# Input_Section.net
KiCad netlist of a schematic drawn in Altium Designer
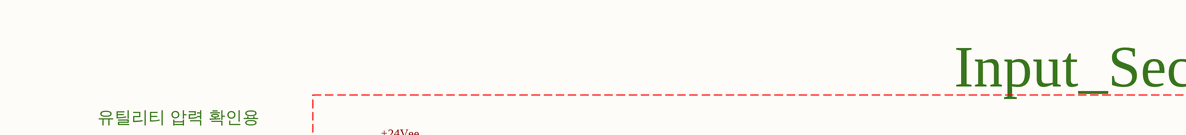
[diagram p0: Input_Section.SchDoc, top left]
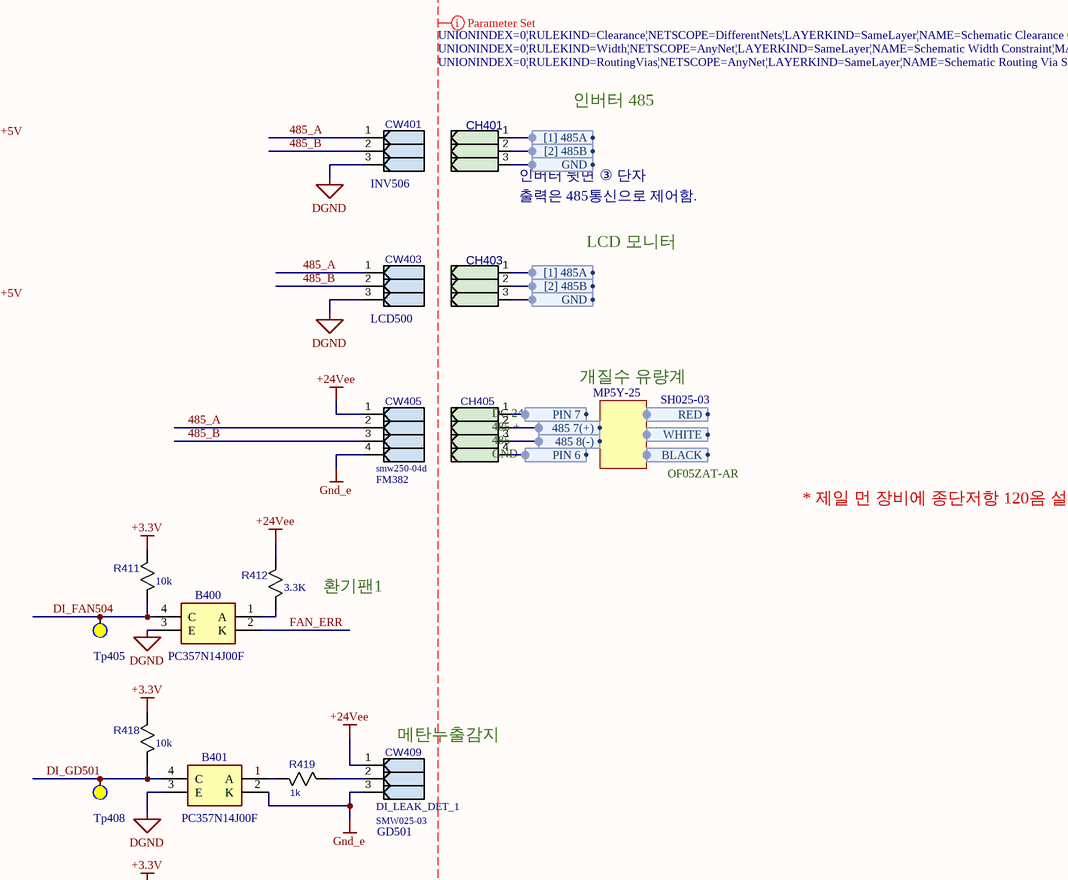
[diagram p1: Input_Section.SchDoc, top right]
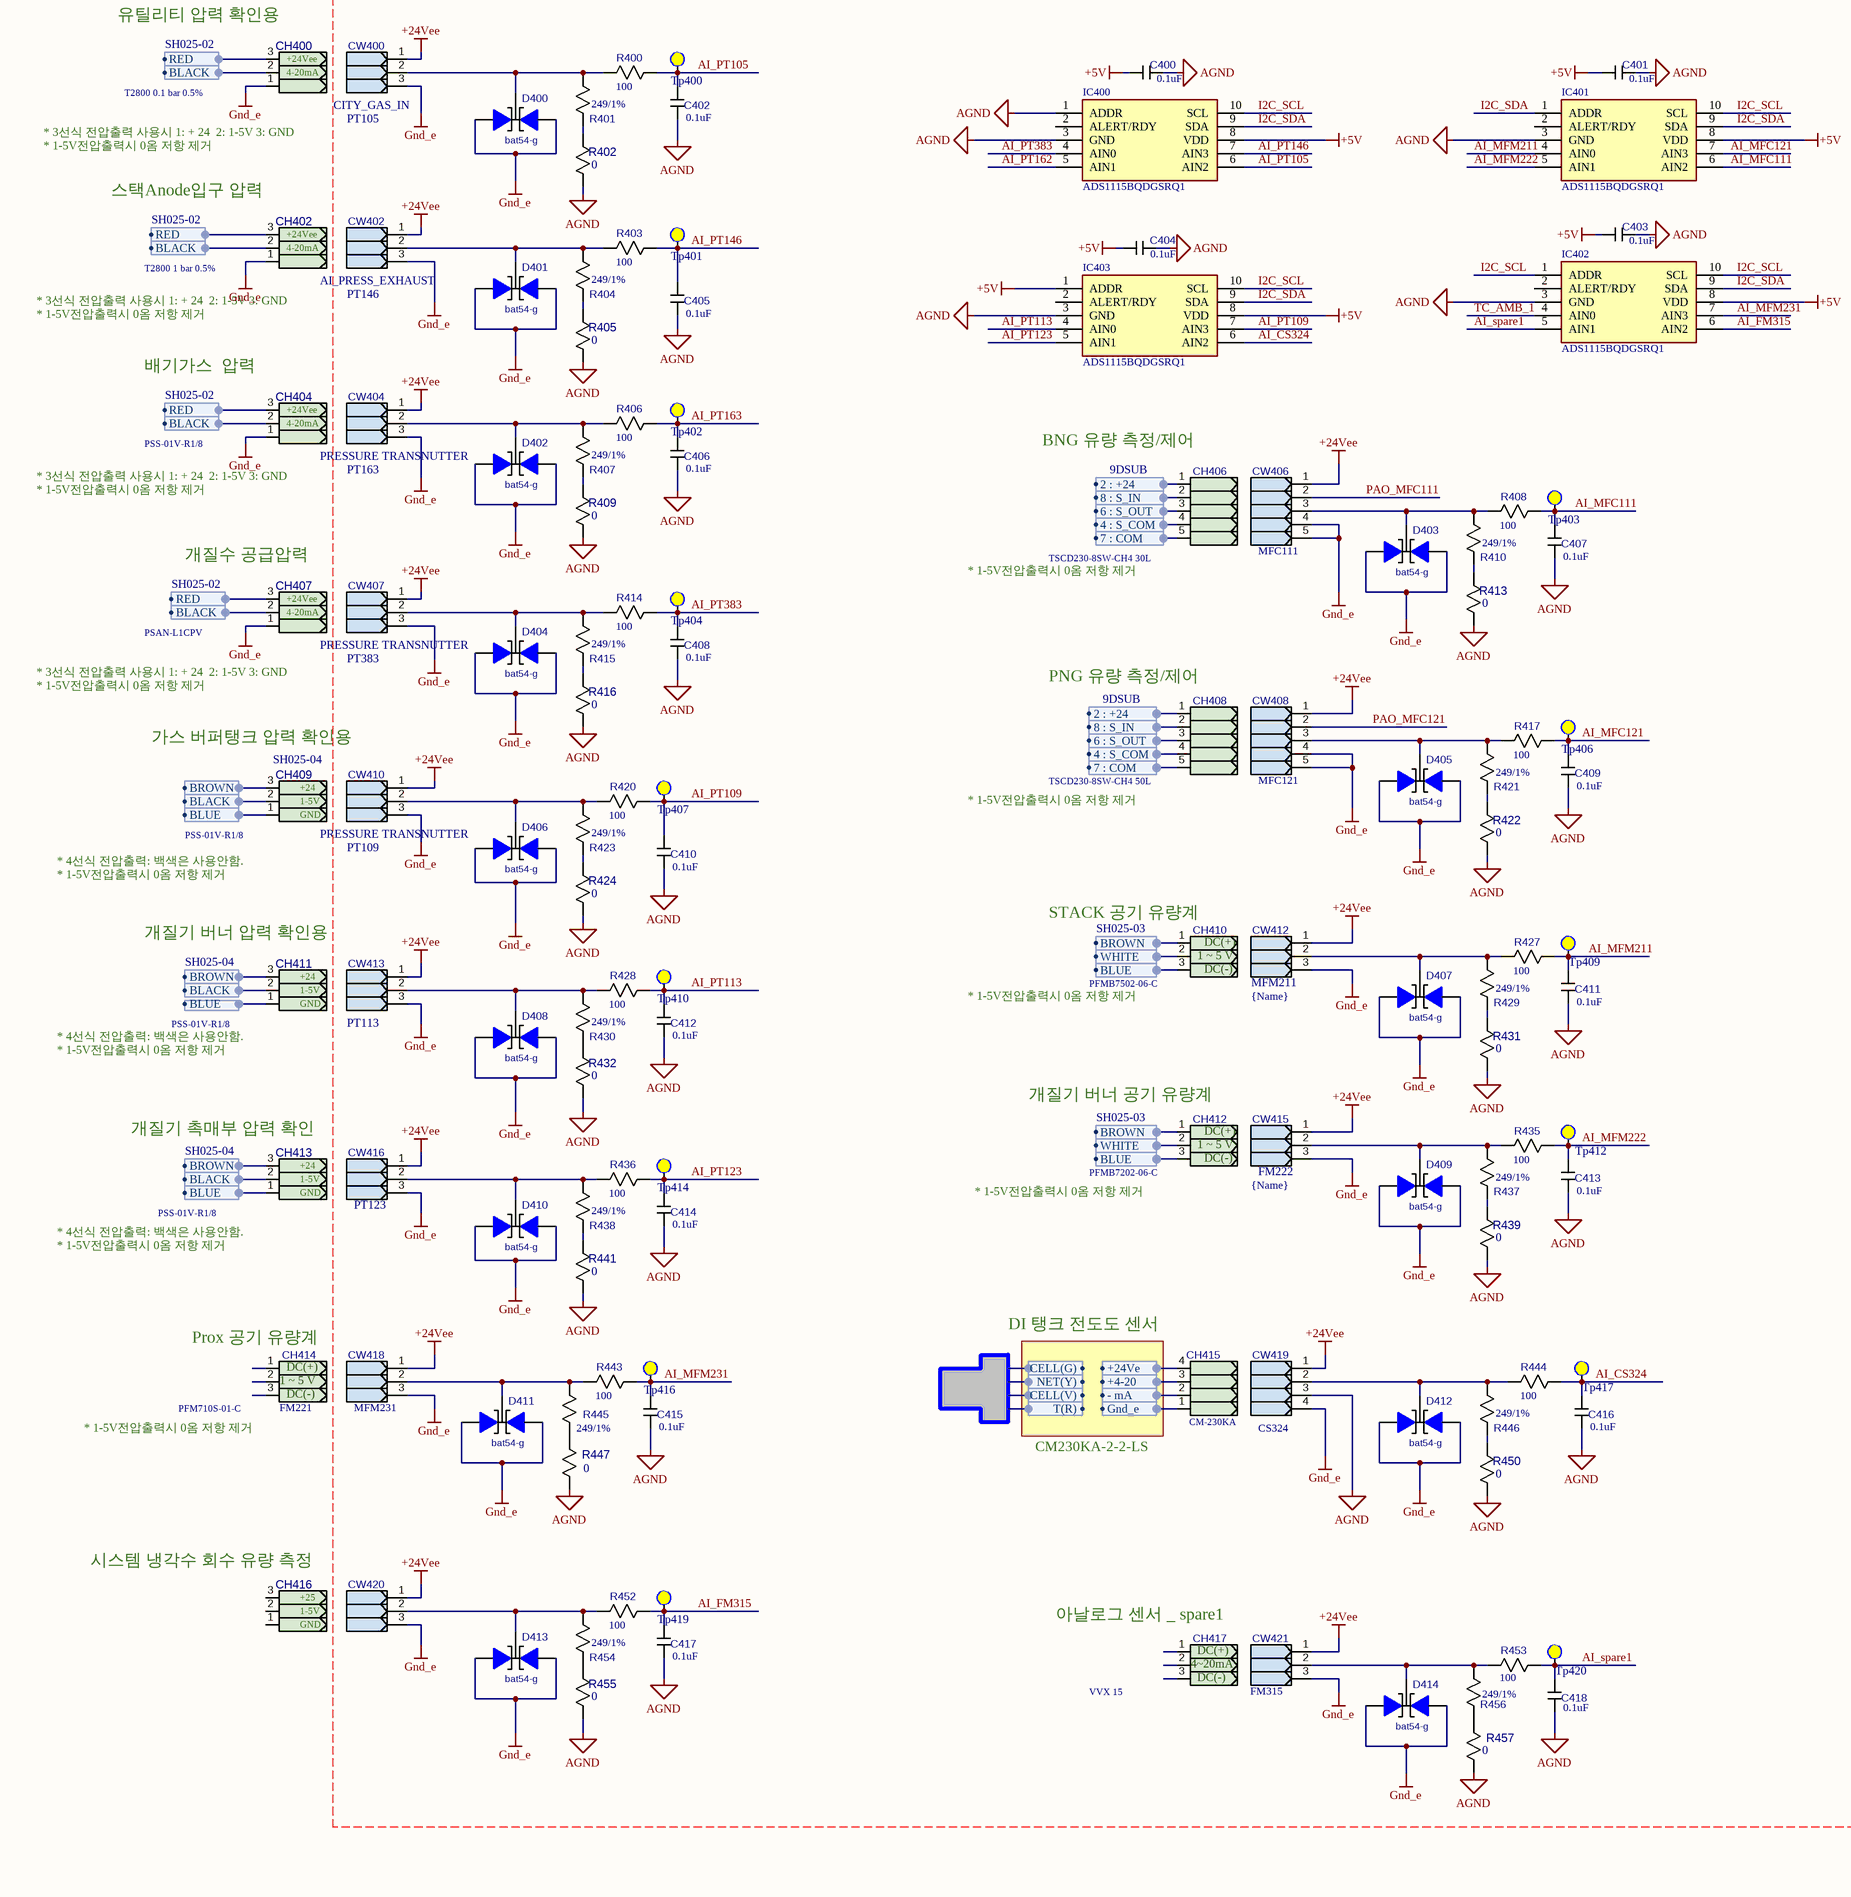
[diagram p2: Input_Section.SchDoc, bottom left]
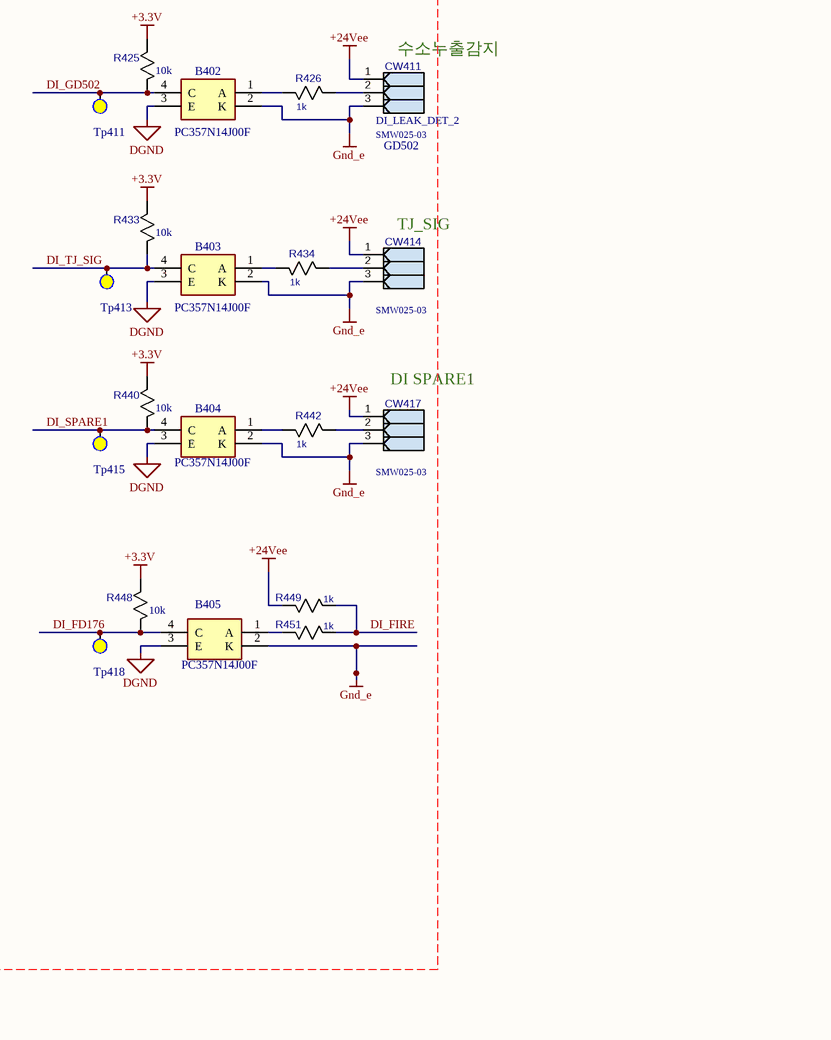
[diagram p3: Input_Section.SchDoc, bottom right]

(export (version "E")
  (design (tool "Eeschema 10.0.6"))
  (components
    (comp (ref "B400")
      (value "PC357N14J00F")
      (footprint "KipoAlt:SOP254P675X300-4N")
      (description "Integrated Circuit")
      (libsource (lib "KipoAlt") (part "PC357N14J00F"))
    )
    (comp (ref "B401")
      (value "PC357N14J00F")
      (footprint "KipoAlt:SOP254P675X300-4N")
      (description "Integrated Circuit")
      (libsource (lib "KipoAlt") (part "PC357N14J00F"))
    )
    (comp (ref "B402")
      (value "PC357N14J00F")
      (footprint "KipoAlt:SOP254P675X300-4N")
      (description "Integrated Circuit")
      (libsource (lib "KipoAlt") (part "PC357N14J00F"))
    )
    (comp (ref "B403")
      (value "PC357N14J00F")
      (footprint "KipoAlt:SOP254P675X300-4N")
      (description "Integrated Circuit")
      (libsource (lib "KipoAlt") (part "PC357N14J00F"))
    )
    (comp (ref "B404")
      (value "PC357N14J00F")
      (footprint "KipoAlt:SOP254P675X300-4N")
      (description "Integrated Circuit")
      (libsource (lib "KipoAlt") (part "PC357N14J00F"))
    )
    (comp (ref "B405")
      (value "PC357N14J00F")
      (footprint "KipoAlt:SOP254P675X300-4N")
      (description "Integrated Circuit")
      (libsource (lib "KipoAlt") (part "PC357N14J00F"))
    )
    (comp (ref "C400")
      (value "CS1608")
      (footprint "CC1608N")
      (fields (field (name "PART NO.") "{Part No}") (field (name "규격") "0.1uF"))
      (libsource (lib "KipoAlt") (part "CS1608"))
    )
    (comp (ref "C401")
      (value "CS1608")
      (footprint "CC1608N")
      (fields (field (name "PART NO.") "{Part No}") (field (name "규격") "0.1uF"))
      (libsource (lib "KipoAlt") (part "CS1608"))
    )
    (comp (ref "C402")
      (value "CS1608")
      (footprint "CC1608N")
      (fields (field (name "PART NO.") "{Part No}") (field (name "규격") "0.1uF"))
      (libsource (lib "KipoAlt") (part "CS1608"))
    )
    (comp (ref "C403")
      (value "CS1608")
      (footprint "CC1608N")
      (fields (field (name "PART NO.") "{Part No}") (field (name "규격") "0.1uF"))
      (libsource (lib "KipoAlt") (part "CS1608"))
    )
    (comp (ref "C404")
      (value "CS1608")
      (footprint "CC1608N")
      (fields (field (name "PART NO.") "{Part No}") (field (name "규격") "0.1uF"))
      (libsource (lib "KipoAlt") (part "CS1608"))
    )
    (comp (ref "C405")
      (value "CS1608")
      (footprint "CC1608N")
      (fields (field (name "PART NO.") "{Part No}") (field (name "규격") "0.1uF"))
      (libsource (lib "KipoAlt") (part "CS1608"))
    )
    (comp (ref "C406")
      (value "CS1608")
      (footprint "CC1608N")
      (fields (field (name "PART NO.") "{Part No}") (field (name "규격") "0.1uF"))
      (libsource (lib "KipoAlt") (part "CS1608"))
    )
    (comp (ref "C407")
      (value "CS1608")
      (footprint "CC1608N")
      (fields (field (name "PART NO.") "{Part No}") (field (name "규격") "0.1uF"))
      (libsource (lib "KipoAlt") (part "CS1608"))
    )
    (comp (ref "C408")
      (value "CS1608")
      (footprint "CC1608N")
      (fields (field (name "PART NO.") "{Part No}") (field (name "규격") "0.1uF"))
      (libsource (lib "KipoAlt") (part "CS1608"))
    )
    (comp (ref "C409")
      (value "CS1608")
      (footprint "CC1608N")
      (fields (field (name "PART NO.") "{Part No}") (field (name "규격") "0.1uF"))
      (libsource (lib "KipoAlt") (part "CS1608"))
    )
    (comp (ref "C410")
      (value "CS1608")
      (footprint "CC1608N")
      (fields (field (name "PART NO.") "{Part No}") (field (name "규격") "0.1uF"))
      (libsource (lib "KipoAlt") (part "CS1608"))
    )
    (comp (ref "C411")
      (value "CS1608")
      (footprint "CC1608N")
      (fields (field (name "PART NO.") "{Part No}") (field (name "규격") "0.1uF"))
      (libsource (lib "KipoAlt") (part "CS1608"))
    )
    (comp (ref "C412")
      (value "CS1608")
      (footprint "CC1608N")
      (fields (field (name "PART NO.") "{Part No}") (field (name "규격") "0.1uF"))
      (libsource (lib "KipoAlt") (part "CS1608"))
    )
    (comp (ref "C413")
      (value "CS1608")
      (footprint "CC1608N")
      (fields (field (name "PART NO.") "{Part No}") (field (name "규격") "0.1uF"))
      (libsource (lib "KipoAlt") (part "CS1608"))
    )
    (comp (ref "C414")
      (value "CS1608")
      (footprint "CC1608N")
      (fields (field (name "PART NO.") "{Part No}") (field (name "규격") "0.1uF"))
      (libsource (lib "KipoAlt") (part "CS1608"))
    )
    (comp (ref "C415")
      (value "CS1608")
      (footprint "CC1608N")
      (fields (field (name "PART NO.") "{Part No}") (field (name "규격") "0.1uF"))
      (libsource (lib "KipoAlt") (part "CS1608"))
    )
    (comp (ref "C416")
      (value "CS1608")
      (footprint "CC1608N")
      (fields (field (name "PART NO.") "{Part No}") (field (name "규격") "0.1uF"))
      (libsource (lib "KipoAlt") (part "CS1608"))
    )
    (comp (ref "C417")
      (value "CS1608")
      (footprint "CC1608N")
      (fields (field (name "PART NO.") "{Part No}") (field (name "규격") "0.1uF"))
      (libsource (lib "KipoAlt") (part "CS1608"))
    )
    (comp (ref "C418")
      (value "CS1608")
      (footprint "CC1608N")
      (fields (field (name "PART NO.") "{Part No}") (field (name "규격") "0.1uF"))
      (libsource (lib "KipoAlt") (part "CS1608"))
    )
    (comp (ref "CH400")
      (value "Connect Housing")
      (description "시티가스 공급압력 확인")
      (fields (field (name "PART NO.") "T2800 0.1 bar 0.5%"))
      (libsource (lib "KipoAlt") (part "CH_03"))
    )
    (comp (ref "CH401") (value "Connect Housing") (libsource (lib "") (part "CH_03_1")))
    (comp (ref "CH402")
      (value "Connect Housing")
      (description "시티가스 공급압력 확인")
      (fields (field (name "PART NO.") "T2800 1 bar 0.5%"))
      (libsource (lib "KipoAlt") (part "CH_03"))
    )
    (comp (ref "CH403") (value "Connect Housing") (libsource (lib "") (part "CH_03_1")))
    (comp (ref "CH404")
      (value "Connect Housing")
      (description "배기가스 출구 압력 측정\r\n\r\nO T2800 1 bar 0.5%")
      (fields (field (name "PART NO.") "PSS-01V-R1/8"))
      (libsource (lib "KipoAlt") (part "CH_03"))
    )
    (comp (ref "CH405")
      (value "Connect Housing")
      (description "개질수 유량계\r\n\r\n사용부품 : OF05ZAT-AR")
      (libsource (lib "KipoAlt") (part "CH_04"))
    )
    (comp (ref "CH406")
      (value "Connect Housing")
      (description "AI_PNG MFC\r\n\r\nTSCD230-6SW-CH4 30L")
      (fields (field (name "PART NO.") "TSCD230-8SW-CH4 30L"))
      (libsource (lib "KipoAlt") (part "CH_05"))
    )
    (comp (ref "CH407")
      (value "Connect Housing")
      (description "개질수 압력\r\n\r\nO T2800 10 bar 0.5%\r\nO 4~20mA\r\n\r\nO T2800 1 bar 0.5%")
      (fields (field (name "PART NO.") "PSAN-L1CPV"))
      (libsource (lib "KipoAlt") (part "CH_03"))
    )
    (comp (ref "CH408")
      (value "Connect Housing")
      (description "AI_PNG MFC\r\n\r\nTSCD230-6SW-CH4 30L")
      (fields (field (name "PART NO.") "TSCD230-8SW-CH4 50L"))
      (libsource (lib "KipoAlt") (part "CH_05"))
    )
    (comp (ref "CH409")
      (value "Connect Housing")
      (description "가압 버퍼탱크 압력 측정\r\n\r\n사용부품 : PSS-01A-R1/8\r\n\r\nO T2800 1 bar 0.5%")
      (fields (field (name "PART NO.") "PSS-01V-R1/8"))
      (libsource (lib "KipoAlt") (part "CH_03"))
    )
    (comp (ref "CH410")
      (value "Connect Housing")
      (description "스택 공기 유량계\r\n\r\nO PFMB7501-04-D\r\nO 1 ~ 5 V 입력 / 4~20mA")
      (fields (field (name "PART NO.") "PFMB7502-06-C"))
      (libsource (lib "") (part "CH_03_2"))
    )
    (comp (ref "CH411")
      (value "Connect Housing")
      (description "개질기 버너 압력 확인용\r\n\r\n사용부품 : PSS-01V-R1/8   \r\n\r\nO T2800 1 bar 0.5%")
      (fields (field (name "PART NO.") "PSS-01V-R1/8"))
      (libsource (lib "KipoAlt") (part "CH_03"))
    )
    (comp (ref "CH412")
      (value "Connect Housing")
      (description "스택 공기 유량계\r\n\r\nO PFMB7501-04-D\r\nO 1 ~ 5 V 입력 / 4~20mA")
      (fields (field (name "PART NO.") "PFMB7202-06-C"))
      (libsource (lib "") (part "CH_03_2"))
    )
    (comp (ref "CH413")
      (value "Connect Housing")
      (description "개질기 촉매부 압력 확인\r\n\r\n사용부품 : PSS-01V-R1/8 \r\n\r\nO T2800 1 bar 0.5%")
      (fields (field (name "PART NO.") "PSS-01V-R1/8"))
      (libsource (lib "KipoAlt") (part "CH_03"))
    )
    (comp (ref "CH414")
      (value "Connect Housing")
      (description "Prox 공기 유량계\r\n\r\nO PFMB7501-04-D\r\nO 1 ~ 5 V 출력")
      (fields (field (name "PART NO.") "PFM710S-01-C") (field (name "BOP NO") "FM221"))
      (libsource (lib "") (part "CH_03_2"))
    )
    (comp (ref "CH415")
      (value "Connect Housing")
      (description "[DI 탱크 전도도 센서]\r\n\r\nO 4~20mA Input")
      (fields (field (name "PART NO.") "CM-230KA"))
      (libsource (lib "") (part "CH_04_1"))
    )
    (comp (ref "CH416")
      (value "Connect Housing")
      (description "개질기 버너 압력 확인용\r\n\r\n사용부품 : PSS-01V-R1/8   \r\n\r\nO T2800 1 bar 0.5%")
      (libsource (lib "KipoAlt") (part "CH_03"))
    )
    (comp (ref "CH417")
      (value "Connect Housing")
      (description "Prox 공기 유량계\r\n\r\nO PFMB7501-04-D\r\nO 1 ~ 5 V 출력")
      (fields (field (name "PART NO.") "VVX 15"))
      (libsource (lib "") (part "CH_03_2"))
    )
    (comp (ref "CW400")
      (value "SMW250-03D")
      (footprint "SMW250-03D")
      (description "{도시가스 입압}\r\n\r\n사용부품 : T2800 0.1 bar 0.5%\r\n시티가스 공급압력 확인")
      (fields
        (field (name "NAME") "CITY_GAS_IN")
        (field (name "PART NO.") "SMW025-03")
        (field (name "BOP NO") "PT105")
      )
      (libsource (lib "KipoAlt") (part "SMW250-03D"))
    )
    (comp (ref "CW401")
      (value "SMW250-03D")
      (footprint "SMW250-03D")
      (fields (field (name "PART NO.") "SMW025-03") (field (name "BOP NO") "INV506"))
      (libsource (lib "") (part "SMW250-03D_1"))
    )
    (comp (ref "CW402")
      (value "SMW250-03D")
      (footprint "SMW250-03D")
      (description "개질가스(스택입구) 압력\r\n\r\n사용부품 : T2800 1 bar 0.5%")
      (fields
        (field (name "NAME") "AI_PRESS_EXHAUST")
        (field (name "PART NO.") "SMW025-03")
        (field (name "BOP NO") "PT146")
      )
      (libsource (lib "KipoAlt") (part "SMW250-03D"))
    )
    (comp (ref "CW403")
      (value "SMW250-03D")
      (footprint "SMW250-03D")
      (fields (field (name "PART NO.") "SMW025-03") (field (name "BOP NO") "LCD500"))
      (libsource (lib "") (part "SMW250-03D_1"))
    )
    (comp (ref "CW404")
      (value "SMW250-03D")
      (footprint "SMW250-03D")
      (description "개질가스(스택입구) 압력\r\n\r\n사용부품 : T2800 1 bar 0.5%")
      (fields
        (field (name "NAME") "PRESSURE TRANSNUTTER")
        (field (name "PART NO.") "SMW025-03")
        (field (name "BOP NO") "PT163")
      )
      (libsource (lib "KipoAlt") (part "SMW250-03D"))
    )
    (comp (ref "CW405")
      (value "SMW250-04D")
      (footprint "SMW250-04D")
      (description "485통신")
      (fields (field (name "PART NO.") "smw250-04d") (field (name "BOP NO") "FM382"))
      (libsource (lib "KipoAlt") (part "SMW250-04D"))
    )
    (comp (ref "CW406")
      (value "SMW250-05D")
      (footprint "SMW250-05D")
      (description "AI_PNG MFC\r\n\r\nTSCD230-6SW-CH4 30L")
      (fields (field (name "PART NO.") "smw025-05") (field (name "BOP NO") "MFC111"))
      (libsource (lib "KipoAlt") (part "SMW250-05D"))
    )
    (comp (ref "CW407")
      (value "SMW250-03D")
      (footprint "SMW250-03D")
      (description "개질기 촉매부 압력 확인\r\nO 사용부품 : T2800 1 bar 0.5%\r\nO 4~20mA Input")
      (fields
        (field (name "NAME") "PRESSURE TRANSNUTTER")
        (field (name "PART NO.") "SMW025-03")
        (field (name "BOP NO") "PT383")
      )
      (libsource (lib "KipoAlt") (part "SMW250-03D"))
    )
    (comp (ref "CW408")
      (value "SMW250-05D")
      (footprint "SMW250-05D")
      (description "AI_PNG MFC\r\n\r\nTSCD230-6SW-CH4 30L")
      (fields (field (name "PART NO.") "smw025-05") (field (name "BOP NO") "MFC121"))
      (libsource (lib "KipoAlt") (part "SMW250-05D"))
    )
    (comp (ref "CW409")
      (value "SMW250-03D")
      (footprint "SMW250-03D")
      (description "GD504 \r\n(메탄가스누출감지기): 가스가 샜을 때 경보(0 또는 1)만 던져주는 순수 상태 감시용 디지털 입력단이야. 고속 처리가 필요 없는 일반 GPIO 특성.")
      (fields
        (field (name "NAME") "DI_LEAK_DET_1")
        (field (name "PART NO.") "SMW025-03")
        (field (name "BOP NO") "GD501")
      )
      (libsource (lib "") (part "SMW250-03D_1"))
    )
    (comp (ref "CW410")
      (value "SMW250-03D")
      (footprint "SMW250-03D")
      (description "가압 버퍼탱크 압력 측정\r\n\r\n사용부품 : PSS-01V-R1/8")
      (fields
        (field (name "NAME") "PRESSURE TRANSNUTTER")
        (field (name "PART NO.") "SMW025-03")
        (field (name "BOP NO") "PT109")
      )
      (libsource (lib "KipoAlt") (part "SMW250-03D"))
    )
    (comp (ref "CW411")
      (value "SMW250-03D")
      (footprint "SMW250-03D")
      (description "GD505 (수소 가스누출감지기): 가스가 샜을 때 경보(0 또는 1)만 던져주는 순수 상태 감시용 디지털 입력단이야. 고속 처리가 필요 없는 일반 GPIO 특성.")
      (fields
        (field (name "NAME") "DI_LEAK_DET_2")
        (field (name "PART NO.") "SMW025-03")
        (field (name "BOP NO") "GD502")
      )
      (libsource (lib "") (part "SMW250-03D_1"))
    )
    (comp (ref "CW412")
      (value "SMW250-03D")
      (footprint "SMW250-03D")
      (fields
        (field (name "NAME") "{Name}")
        (field (name "PART NO.") "SMW025-03")
        (field (name "BOP NO") "MFM211")
      )
      (libsource (lib "KipoAlt") (part "SMW250-03D"))
    )
    (comp (ref "CW413")
      (value "SMW250-03D")
      (footprint "SMW250-03D")
      (description "개질기 버너 압력 확인용\r\n\r\n사용부품 : PSS-01V-R1/8")
      (fields (field (name "PART NO.") "SMW025-03") (field (name "BOP NO") "PT113"))
      (libsource (lib "KipoAlt") (part "SMW250-03D"))
    )
    (comp (ref "CW414")
      (value "SMW250-03D")
      (footprint "SMW250-03D")
      (fields (field (name "PART NO.") "SMW025-03"))
      (libsource (lib "") (part "SMW250-03D_1"))
    )
    (comp (ref "CW415")
      (value "SMW250-03D")
      (footprint "SMW250-03D")
      (fields
        (field (name "NAME") "{Name}")
        (field (name "PART NO.") "SMW025-03")
        (field (name "BOP NO") "FM222")
      )
      (libsource (lib "KipoAlt") (part "SMW250-03D"))
    )
    (comp (ref "CW416")
      (value "SMW250-03D")
      (footprint "SMW250-03D")
      (description "개질기 촉매부 압력 확인\r\n\r\n사용부품 : PSS-01V-R1/8")
      (fields (field (name "PART NO.") "SMW025-03") (field (name "BOP NO") "PT123"))
      (libsource (lib "KipoAlt") (part "SMW250-03D"))
    )
    (comp (ref "CW417")
      (value "SMW250-03D")
      (footprint "SMW250-03D")
      (description "GD505 (수소 가스누출감지기): 가스가 샜을 때 경보(0 또는 1)만 던져주는 순수 상태 감시용 디지털 입력단이야. 고속 처리가 필요 없는 일반 GPIO 특성.")
      (fields (field (name "PART NO.") "SMW025-03"))
      (libsource (lib "") (part "SMW250-03D_1"))
    )
    (comp (ref "CW418")
      (value "SMW250-03D")
      (footprint "SMW250-03D")
      (fields (field (name "PART NO.") "SMW025-03") (field (name "BOP NO") "MFM231"))
      (libsource (lib "KipoAlt") (part "SMW250-03D"))
    )
    (comp (ref "CW419")
      (value "SMW250-04D")
      (footprint "SMW250-04D")
      (description "[DI 탱크 전도도 센서]\r\n\r\nO 4~20mA Input[DI 탱크 전도도 센서]")
      (fields (field (name "PART NO.") "smw250-04d") (field (name "BOP NO") "CS324"))
      (libsource (lib "") (part "SMW250-04D_1"))
    )
    (comp (ref "CW420")
      (value "SMW250-03D")
      (footprint "SMW250-03D")
      (description "개질기 버너 압력 확인용\r\n\r\n사용부품 : PSS-01V-R1/8")
      (fields (field (name "PART NO.") "SMW025-03"))
      (libsource (lib "KipoAlt") (part "SMW250-03D"))
    )
    (comp (ref "CW421")
      (value "SMW250-03D")
      (footprint "SMW250-03D")
      (fields (field (name "PART NO.") "SMW025-03") (field (name "BOP NO") "FM315"))
      (libsource (lib "KipoAlt") (part "SMW250-03D"))
    )
    (comp (ref "D400")
      (value "BAT54C-G")
      (footprint "SOT-23")
      (fields (field (name "PART NO.") "bat54-g"))
      (libsource (lib "KipoAlt") (part "BAT54C-G"))
    )
    (comp (ref "D401")
      (value "BAT54C-G")
      (footprint "SOT-23")
      (fields (field (name "PART NO.") "bat54-g"))
      (libsource (lib "KipoAlt") (part "BAT54C-G"))
    )
    (comp (ref "D402")
      (value "BAT54C-G")
      (footprint "SOT-23")
      (fields (field (name "PART NO.") "bat54-g"))
      (libsource (lib "KipoAlt") (part "BAT54C-G"))
    )
    (comp (ref "D403")
      (value "BAT54C-G")
      (footprint "SOT-23")
      (fields (field (name "PART NO.") "bat54-g"))
      (libsource (lib "KipoAlt") (part "BAT54C-G"))
    )
    (comp (ref "D404")
      (value "BAT54C-G")
      (footprint "SOT-23")
      (fields (field (name "PART NO.") "bat54-g"))
      (libsource (lib "KipoAlt") (part "BAT54C-G"))
    )
    (comp (ref "D405")
      (value "BAT54C-G")
      (footprint "SOT-23")
      (fields (field (name "PART NO.") "bat54-g"))
      (libsource (lib "KipoAlt") (part "BAT54C-G"))
    )
    (comp (ref "D406")
      (value "BAT54C-G")
      (footprint "SOT-23")
      (fields (field (name "PART NO.") "bat54-g"))
      (libsource (lib "KipoAlt") (part "BAT54C-G"))
    )
    (comp (ref "D407")
      (value "BAT54C-G")
      (footprint "SOT-23")
      (fields (field (name "PART NO.") "bat54-g"))
      (libsource (lib "KipoAlt") (part "BAT54C-G"))
    )
    (comp (ref "D408")
      (value "BAT54C-G")
      (footprint "SOT-23")
      (fields (field (name "PART NO.") "bat54-g"))
      (libsource (lib "KipoAlt") (part "BAT54C-G"))
    )
    (comp (ref "D409")
      (value "BAT54C-G")
      (footprint "SOT-23")
      (fields (field (name "PART NO.") "bat54-g"))
      (libsource (lib "KipoAlt") (part "BAT54C-G"))
    )
    (comp (ref "D410")
      (value "BAT54C-G")
      (footprint "SOT-23")
      (fields (field (name "PART NO.") "bat54-g"))
      (libsource (lib "KipoAlt") (part "BAT54C-G"))
    )
    (comp (ref "D411")
      (value "BAT54C-G")
      (footprint "SOT-23")
      (fields (field (name "PART NO.") "bat54-g"))
      (libsource (lib "KipoAlt") (part "BAT54C-G"))
    )
    (comp (ref "D412")
      (value "BAT54C-G")
      (footprint "SOT-23")
      (fields (field (name "PART NO.") "bat54-g"))
      (libsource (lib "KipoAlt") (part "BAT54C-G"))
    )
    (comp (ref "D413")
      (value "BAT54C-G")
      (footprint "SOT-23")
      (fields (field (name "PART NO.") "bat54-g"))
      (libsource (lib "KipoAlt") (part "BAT54C-G"))
    )
    (comp (ref "D414")
      (value "BAT54C-G")
      (footprint "SOT-23")
      (fields (field (name "PART NO.") "bat54-g"))
      (libsource (lib "KipoAlt") (part "BAT54C-G"))
    )
    (comp (ref "IC400")
      (value "ADS1115BQDGSRQ1")
      (footprint "KipoAlt:SOP50P490X110-10N")
      (description "Integrated Circuit")
      (libsource (lib "*") (part "ADS1115BQDGSRQ1"))
    )
    (comp (ref "IC401")
      (value "ADS1115BQDGSRQ1")
      (footprint "KipoAlt:SOP50P490X110-10N")
      (description "Integrated Circuit")
      (libsource (lib "*") (part "ADS1115BQDGSRQ1"))
    )
    (comp (ref "IC402")
      (value "ADS1115BQDGSRQ1")
      (footprint "KipoAlt:SOP50P490X110-10N")
      (description "Integrated Circuit")
      (libsource (lib "*") (part "ADS1115BQDGSRQ1"))
    )
    (comp (ref "IC403")
      (value "ADS1115BQDGSRQ1")
      (footprint "KipoAlt:SOP50P490X110-10N")
      (description "Integrated Circuit")
      (libsource (lib "*") (part "ADS1115BQDGSRQ1"))
    )
    (comp (ref "R400")
      (value "R1608")
      (footprint "RESC1608X55N")
      (fields (field (name "규격") "100") (field (name "PART NO.") "WR06X101JT(100R)J"))
      (libsource (lib "KipoAlt") (part "R1608"))
    )
    (comp (ref "R401")
      (value "R1608")
      (footprint "RESC1608X55N")
      (fields (field (name "규격") "249/1%") (field (name "PART NO.") "WR06X2490FT(249R)F"))
      (libsource (lib "KipoAlt") (part "R1608"))
    )
    (comp (ref "R402")
      (value "R3216")
      (footprint "R3216")
      (fields (field (name "규격") "0") (field (name "PART NO.") "WR12X000PT(0R)J"))
      (libsource (lib "KipoAlt") (part "R3216"))
    )
    (comp (ref "R403")
      (value "R1608")
      (footprint "RESC1608X55N")
      (fields (field (name "규격") "100") (field (name "PART NO.") "WR06X101JT(100R)J"))
      (libsource (lib "KipoAlt") (part "R1608"))
    )
    (comp (ref "R404")
      (value "R1608")
      (footprint "RESC1608X55N")
      (fields (field (name "규격") "249/1%") (field (name "PART NO.") "WR06X2490FT(249R)F"))
      (libsource (lib "KipoAlt") (part "R1608"))
    )
    (comp (ref "R405")
      (value "R3216")
      (footprint "R3216")
      (fields (field (name "규격") "0") (field (name "PART NO.") "WR12X000PT(0R)J"))
      (libsource (lib "KipoAlt") (part "R3216"))
    )
    (comp (ref "R406")
      (value "R1608")
      (footprint "RESC1608X55N")
      (fields (field (name "규격") "100") (field (name "PART NO.") "WR06X101JT(100R)J"))
      (libsource (lib "KipoAlt") (part "R1608"))
    )
    (comp (ref "R407")
      (value "R1608")
      (footprint "RESC1608X55N")
      (fields (field (name "규격") "249/1%") (field (name "PART NO.") "WR06X2490FT(249R)F"))
      (libsource (lib "KipoAlt") (part "R1608"))
    )
    (comp (ref "R408")
      (value "R1608")
      (footprint "RESC1608X55N")
      (fields (field (name "규격") "100") (field (name "PART NO.") "WR06X101JT(100R)J"))
      (libsource (lib "KipoAlt") (part "R1608"))
    )
    (comp (ref "R409")
      (value "R3216")
      (footprint "R3216")
      (fields (field (name "규격") "0") (field (name "PART NO.") "WR12X000PT(0R)J"))
      (libsource (lib "KipoAlt") (part "R3216"))
    )
    (comp (ref "R410")
      (value "R1608")
      (footprint "RESC1608X55N")
      (fields (field (name "규격") "249/1%") (field (name "PART NO.") "WR06X2490FT(249R)F"))
      (libsource (lib "KipoAlt") (part "R1608"))
    )
    (comp (ref "R411")
      (value "R1608")
      (footprint "RESC1608X55N")
      (fields (field (name "규격") "10k") (field (name "PART NO.") "WR06X103JT(10KR)J"))
      (libsource (lib "KipoAlt") (part "R1608"))
    )
    (comp (ref "R412")
      (value "R1608")
      (footprint "RESC1608X55N")
      (fields (field (name "규격") "3.3K") (field (name "PART NO.") "WR06X332JT(3.3KR)J"))
      (libsource (lib "KipoAlt") (part "R1608"))
    )
    (comp (ref "R413")
      (value "R3216")
      (footprint "R3216")
      (fields (field (name "규격") "0") (field (name "PART NO.") "WR12X000PT(0R)J"))
      (libsource (lib "KipoAlt") (part "R3216"))
    )
    (comp (ref "R414")
      (value "R1608")
      (footprint "RESC1608X55N")
      (fields (field (name "규격") "100") (field (name "PART NO.") "WR06X101JT(100R)J"))
      (libsource (lib "KipoAlt") (part "R1608"))
    )
    (comp (ref "R415")
      (value "R1608")
      (footprint "RESC1608X55N")
      (fields (field (name "규격") "249/1%") (field (name "PART NO.") "WR06X2490FT(249R)F"))
      (libsource (lib "KipoAlt") (part "R1608"))
    )
    (comp (ref "R416")
      (value "R3216")
      (footprint "R3216")
      (fields (field (name "규격") "0") (field (name "PART NO.") "WR12X000PT(0R)J"))
      (libsource (lib "KipoAlt") (part "R3216"))
    )
    (comp (ref "R417")
      (value "R1608")
      (footprint "RESC1608X55N")
      (fields (field (name "규격") "100") (field (name "PART NO.") "WR06X101JT(100R)J"))
      (libsource (lib "KipoAlt") (part "R1608"))
    )
    (comp (ref "R418")
      (value "R1608")
      (footprint "RESC1608X55N")
      (fields (field (name "규격") "10k") (field (name "PART NO.") "WR06X103JT(10KR)J"))
      (libsource (lib "KipoAlt") (part "R1608"))
    )
    (comp (ref "R419")
      (value "R2012")
      (footprint "R2012")
      (fields (field (name "PART NO.") "1k"))
      (libsource (lib "KipoAlt") (part "R2012"))
    )
    (comp (ref "R420")
      (value "R1608")
      (footprint "RESC1608X55N")
      (fields (field (name "규격") "100") (field (name "PART NO.") "WR06X101JT(100R)J"))
      (libsource (lib "KipoAlt") (part "R1608"))
    )
    (comp (ref "R421")
      (value "R1608")
      (footprint "RESC1608X55N")
      (fields (field (name "규격") "249/1%") (field (name "PART NO.") "WR06X2490FT(249R)F"))
      (libsource (lib "KipoAlt") (part "R1608"))
    )
    (comp (ref "R422")
      (value "R3216")
      (footprint "R3216")
      (fields (field (name "규격") "0") (field (name "PART NO.") "WR12X000PT(0R)J"))
      (libsource (lib "KipoAlt") (part "R3216"))
    )
    (comp (ref "R423")
      (value "R1608")
      (footprint "RESC1608X55N")
      (fields (field (name "규격") "249/1%") (field (name "PART NO.") "WR06X2490FT(249R)F"))
      (libsource (lib "KipoAlt") (part "R1608"))
    )
    (comp (ref "R424")
      (value "R3216")
      (footprint "R3216")
      (fields (field (name "규격") "0") (field (name "PART NO.") "WR12X000PT(0R)J"))
      (libsource (lib "KipoAlt") (part "R3216"))
    )
    (comp (ref "R425")
      (value "R1608")
      (footprint "RESC1608X55N")
      (fields (field (name "규격") "10k") (field (name "PART NO.") "WR06X103JT(10KR)J"))
      (libsource (lib "KipoAlt") (part "R1608"))
    )
    (comp (ref "R426")
      (value "R2012")
      (footprint "R2012")
      (fields (field (name "PART NO.") "1k"))
      (libsource (lib "KipoAlt") (part "R2012"))
    )
    (comp (ref "R427")
      (value "R1608")
      (footprint "RESC1608X55N")
      (fields (field (name "규격") "100") (field (name "PART NO.") "WR06X101JT(100R)J"))
      (libsource (lib "KipoAlt") (part "R1608"))
    )
    (comp (ref "R428")
      (value "R1608")
      (footprint "RESC1608X55N")
      (fields (field (name "규격") "100") (field (name "PART NO.") "WR06X101JT(100R)J"))
      (libsource (lib "KipoAlt") (part "R1608"))
    )
    (comp (ref "R429")
      (value "R1608")
      (footprint "RESC1608X55N")
      (fields (field (name "규격") "249/1%") (field (name "PART NO.") "WR06X2490FT(249R)F"))
      (libsource (lib "KipoAlt") (part "R1608"))
    )
    (comp (ref "R430")
      (value "R1608")
      (footprint "RESC1608X55N")
      (fields (field (name "규격") "249/1%") (field (name "PART NO.") "WR06X2490FT(249R)F"))
      (libsource (lib "KipoAlt") (part "R1608"))
    )
    (comp (ref "R431")
      (value "R3216")
      (footprint "R3216")
      (fields (field (name "규격") "0") (field (name "PART NO.") "WR12X000PT(0R)J"))
      (libsource (lib "KipoAlt") (part "R3216"))
    )
    (comp (ref "R432")
      (value "R3216")
      (footprint "R3216")
      (fields (field (name "규격") "0") (field (name "PART NO.") "WR12X000PT(0R)J"))
      (libsource (lib "KipoAlt") (part "R3216"))
    )
    (comp (ref "R433")
      (value "R1608")
      (footprint "RESC1608X55N")
      (fields (field (name "규격") "10k") (field (name "PART NO.") "WR06X103JT(10KR)J"))
      (libsource (lib "KipoAlt") (part "R1608"))
    )
    (comp (ref "R434")
      (value "R2012")
      (footprint "R2012")
      (fields (field (name "PART NO.") "1k"))
      (libsource (lib "KipoAlt") (part "R2012"))
    )
    (comp (ref "R435")
      (value "R1608")
      (footprint "RESC1608X55N")
      (fields (field (name "규격") "100") (field (name "PART NO.") "WR06X101JT(100R)J"))
      (libsource (lib "KipoAlt") (part "R1608"))
    )
    (comp (ref "R436")
      (value "R1608")
      (footprint "RESC1608X55N")
      (fields (field (name "규격") "100") (field (name "PART NO.") "WR06X101JT(100R)J"))
      (libsource (lib "KipoAlt") (part "R1608"))
    )
    (comp (ref "R437")
      (value "R1608")
      (footprint "RESC1608X55N")
      (fields (field (name "규격") "249/1%") (field (name "PART NO.") "WR06X2490FT(249R)F"))
      (libsource (lib "KipoAlt") (part "R1608"))
    )
    (comp (ref "R438")
      (value "R1608")
      (footprint "RESC1608X55N")
      (fields (field (name "규격") "249/1%") (field (name "PART NO.") "WR06X2490FT(249R)F"))
      (libsource (lib "KipoAlt") (part "R1608"))
    )
    (comp (ref "R439")
      (value "R3216")
      (footprint "R3216")
      (fields (field (name "규격") "0") (field (name "PART NO.") "WR12X000PT(0R)J"))
      (libsource (lib "KipoAlt") (part "R3216"))
    )
    (comp (ref "R440")
      (value "R1608")
      (footprint "RESC1608X55N")
      (fields (field (name "규격") "10k") (field (name "PART NO.") "WR06X103JT(10KR)J"))
      (libsource (lib "KipoAlt") (part "R1608"))
    )
    (comp (ref "R441")
      (value "R3216")
      (footprint "R3216")
      (fields (field (name "규격") "0") (field (name "PART NO.") "WR12X000PT(0R)J"))
      (libsource (lib "KipoAlt") (part "R3216"))
    )
    (comp (ref "R442")
      (value "R2012")
      (footprint "R2012")
      (fields (field (name "PART NO.") "1k"))
      (libsource (lib "KipoAlt") (part "R2012"))
    )
    (comp (ref "R443")
      (value "R1608")
      (footprint "RESC1608X55N")
      (fields (field (name "규격") "100") (field (name "PART NO.") "WR06X101JT(100R)J"))
      (libsource (lib "KipoAlt") (part "R1608"))
    )
    (comp (ref "R444")
      (value "R1608")
      (footprint "RESC1608X55N")
      (fields (field (name "규격") "100") (field (name "PART NO.") "WR06X101JT(100R)J"))
      (libsource (lib "KipoAlt") (part "R1608"))
    )
    (comp (ref "R445")
      (value "R1608")
      (footprint "RESC1608X55N")
      (fields (field (name "규격") "249/1%") (field (name "PART NO.") "WR06X2490FT(249R)F"))
      (libsource (lib "KipoAlt") (part "R1608"))
    )
    (comp (ref "R446")
      (value "R1608")
      (footprint "RESC1608X55N")
      (fields (field (name "규격") "249/1%") (field (name "PART NO.") "WR06X2490FT(249R)F"))
      (libsource (lib "KipoAlt") (part "R1608"))
    )
    (comp (ref "R447")
      (value "R3216")
      (footprint "R3216")
      (fields (field (name "규격") "0") (field (name "PART NO.") "WR12X000PT(0R)J"))
      (libsource (lib "KipoAlt") (part "R3216"))
    )
    (comp (ref "R448")
      (value "R1608")
      (footprint "RESC1608X55N")
      (fields (field (name "규격") "10k") (field (name "PART NO.") "WR06X103JT(10KR)J"))
      (libsource (lib "KipoAlt") (part "R1608"))
    )
    (comp (ref "R449")
      (value "R2012")
      (footprint "R2012")
      (fields (field (name "PART NO.") "1k"))
      (libsource (lib "KipoAlt") (part "R2012"))
    )
    (comp (ref "R450")
      (value "R3216")
      (footprint "R3216")
      (fields (field (name "규격") "0") (field (name "PART NO.") "WR12X000PT(0R)J"))
      (libsource (lib "KipoAlt") (part "R3216"))
    )
    (comp (ref "R451")
      (value "R2012")
      (footprint "R2012")
      (fields (field (name "PART NO.") "1k"))
      (libsource (lib "KipoAlt") (part "R2012"))
    )
    (comp (ref "R452")
      (value "R1608")
      (footprint "RESC1608X55N")
      (fields (field (name "규격") "100") (field (name "PART NO.") "WR06X101JT(100R)J"))
      (libsource (lib "KipoAlt") (part "R1608"))
    )
    (comp (ref "R453")
      (value "R1608")
      (footprint "RESC1608X55N")
      (fields (field (name "규격") "100") (field (name "PART NO.") "WR06X101JT(100R)J"))
      (libsource (lib "KipoAlt") (part "R1608"))
    )
    (comp (ref "R454")
      (value "R1608")
      (footprint "RESC1608X55N")
      (fields (field (name "규격") "249/1%") (field (name "PART NO.") "WR06X2490FT(249R)F"))
      (libsource (lib "KipoAlt") (part "R1608"))
    )
    (comp (ref "R455")
      (value "R3216")
      (footprint "R3216")
      (fields (field (name "규격") "0") (field (name "PART NO.") "WR12X000PT(0R)J"))
      (libsource (lib "KipoAlt") (part "R3216"))
    )
    (comp (ref "R456")
      (value "R1608")
      (footprint "RESC1608X55N")
      (fields (field (name "규격") "249/1%") (field (name "PART NO.") "WR06X2490FT(249R)F"))
      (libsource (lib "KipoAlt") (part "R1608"))
    )
    (comp (ref "R457")
      (value "R3216")
      (footprint "R3216")
      (fields (field (name "규격") "0") (field (name "PART NO.") "WR12X000PT(0R)J"))
      (libsource (lib "KipoAlt") (part "R3216"))
    )
    (comp (ref "Tp400")
      (value "Test Point_top")
      (footprint "TP_KEYSTONE_5000")
      (description "Pad30")
      (libsource (lib "KipoAlt") (part "Tp_5000"))
    )
    (comp (ref "Tp401")
      (value "Test Point_top")
      (footprint "TP_KEYSTONE_5000")
      (description "Pad30")
      (libsource (lib "KipoAlt") (part "Tp_5000"))
    )
    (comp (ref "Tp402")
      (value "Test Point_top")
      (footprint "TP_KEYSTONE_5000")
      (description "Pad30")
      (libsource (lib "KipoAlt") (part "Tp_5000"))
    )
    (comp (ref "Tp403")
      (value "Test Point_top")
      (footprint "TP_KEYSTONE_5000")
      (description "Pad30")
      (libsource (lib "KipoAlt") (part "Tp_5000"))
    )
    (comp (ref "Tp404")
      (value "Test Point_top")
      (footprint "TP_KEYSTONE_5000")
      (description "Pad30")
      (libsource (lib "KipoAlt") (part "Tp_5000"))
    )
    (comp (ref "Tp405")
      (value "Test Point_top")
      (footprint "TP_KEYSTONE_5000")
      (description "Pad30")
      (libsource (lib "KipoAlt") (part "Tp_5000"))
    )
    (comp (ref "Tp406")
      (value "Test Point_top")
      (footprint "TP_KEYSTONE_5000")
      (description "Pad30")
      (libsource (lib "KipoAlt") (part "Tp_5000"))
    )
    (comp (ref "Tp407")
      (value "Test Point_top")
      (footprint "TP_KEYSTONE_5000")
      (description "Pad30")
      (libsource (lib "KipoAlt") (part "Tp_5000"))
    )
    (comp (ref "Tp408")
      (value "Test Point_top")
      (footprint "TP_KEYSTONE_5000")
      (description "Pad30")
      (libsource (lib "KipoAlt") (part "Tp_5000"))
    )
    (comp (ref "Tp409")
      (value "Test Point_top")
      (footprint "TP_KEYSTONE_5000")
      (description "Pad30")
      (libsource (lib "KipoAlt") (part "Tp_5000"))
    )
    (comp (ref "Tp410")
      (value "Test Point_top")
      (footprint "TP_KEYSTONE_5000")
      (description "Pad30")
      (libsource (lib "KipoAlt") (part "Tp_5000"))
    )
    (comp (ref "Tp411")
      (value "Test Point_top")
      (footprint "TP_KEYSTONE_5000")
      (description "Pad30")
      (libsource (lib "KipoAlt") (part "Tp_5000"))
    )
    (comp (ref "Tp412")
      (value "Test Point_top")
      (footprint "TP_KEYSTONE_5000")
      (description "Pad30")
      (libsource (lib "KipoAlt") (part "Tp_5000"))
    )
    (comp (ref "Tp413")
      (value "Test Point_top")
      (footprint "TP_KEYSTONE_5000")
      (description "Pad30")
      (libsource (lib "KipoAlt") (part "Tp_5000"))
    )
    (comp (ref "Tp414")
      (value "Test Point_top")
      (footprint "TP_KEYSTONE_5000")
      (description "Pad30")
      (libsource (lib "KipoAlt") (part "Tp_5000"))
    )
    (comp (ref "Tp415")
      (value "Test Point_top")
      (footprint "TP_KEYSTONE_5000")
      (description "Pad30")
      (libsource (lib "KipoAlt") (part "Tp_5000"))
    )
    (comp (ref "Tp416")
      (value "Test Point_top")
      (footprint "TP_KEYSTONE_5000")
      (description "Pad30")
      (libsource (lib "KipoAlt") (part "Tp_5000"))
    )
    (comp (ref "Tp417")
      (value "Test Point_top")
      (footprint "TP_KEYSTONE_5000")
      (description "Pad30")
      (libsource (lib "KipoAlt") (part "Tp_5000"))
    )
    (comp (ref "Tp418")
      (value "Test Point_top")
      (footprint "TP_KEYSTONE_5000")
      (description "Pad30")
      (libsource (lib "KipoAlt") (part "Tp_5000"))
    )
    (comp (ref "Tp419")
      (value "Test Point_top")
      (footprint "TP_KEYSTONE_5000")
      (description "Pad30")
      (libsource (lib "KipoAlt") (part "Tp_5000"))
    )
    (comp (ref "Tp420")
      (value "Test Point_top")
      (footprint "TP_KEYSTONE_5000")
      (description "Pad30")
      (libsource (lib "KipoAlt") (part "Tp_5000"))
    )
  )
  (nets
    (net (code "1") (name "+3.3V") (class "Default")
      (node (ref "R411") (pin "2") (pintype "passive"))
      (node (ref "R418") (pin "2") (pintype "passive"))
      (node (ref "R425") (pin "2") (pintype "passive"))
      (node (ref "R433") (pin "2") (pintype "passive"))
      (node (ref "R440") (pin "2") (pintype "passive"))
      (node (ref "R448") (pin "2") (pintype "passive"))
    )
    (net (code "2") (name "+5V") (class "Default")
      (node (ref "C400") (pin "1") (pintype "passive"))
      (node (ref "C401") (pin "1") (pintype "passive"))
      (node (ref "C403") (pin "1") (pintype "passive"))
      (node (ref "C404") (pin "1") (pintype "passive"))
      (node (ref "IC400") (pin "8") (pinfunction "VDD_8") (pintype "passive"))
      (node (ref "IC401") (pin "8") (pinfunction "VDD_8") (pintype "passive"))
      (node (ref "IC402") (pin "8") (pinfunction "VDD_8") (pintype "passive"))
      (node (ref "IC403") (pin "1") (pinfunction "ADDR_1") (pintype "passive"))
      (node (ref "IC403") (pin "8") (pinfunction "VDD_8") (pintype "passive"))
    )
    (net (code "3") (name "+24Vee") (class "Default")
      (node (ref "CW400") (pin "1") (pintype "passive"))
      (node (ref "CW402") (pin "1") (pintype "passive"))
      (node (ref "CW404") (pin "1") (pintype "passive"))
      (node (ref "CW405") (pin "1") (pintype "passive"))
      (node (ref "CW406") (pin "1") (pintype "passive"))
      (node (ref "CW407") (pin "1") (pintype "passive"))
      (node (ref "CW408") (pin "1") (pintype "passive"))
      (node (ref "CW409") (pin "1") (pintype "passive"))
      (node (ref "CW410") (pin "1") (pintype "passive"))
      (node (ref "CW411") (pin "1") (pintype "passive"))
      (node (ref "CW412") (pin "1") (pintype "passive"))
      (node (ref "CW413") (pin "1") (pintype "passive"))
      (node (ref "CW414") (pin "1") (pintype "passive"))
      (node (ref "CW415") (pin "1") (pintype "passive"))
      (node (ref "CW416") (pin "1") (pintype "passive"))
      (node (ref "CW417") (pin "1") (pintype "passive"))
      (node (ref "CW418") (pin "1") (pintype "passive"))
      (node (ref "CW419") (pin "1") (pintype "passive"))
      (node (ref "CW420") (pin "1") (pintype "passive"))
      (node (ref "CW421") (pin "1") (pintype "passive"))
      (node (ref "R412") (pin "2") (pintype "passive"))
      (node (ref "R449") (pin "2") (pintype "passive"))
    )
    (net (code "4") (name "/485_A") (class "Default")
      (node (ref "CW401") (pin "1") (pintype "passive"))
      (node (ref "CW403") (pin "1") (pintype "passive"))
      (node (ref "CW405") (pin "2") (pintype "passive"))
    )
    (net (code "5") (name "/485_B") (class "Default")
      (node (ref "CW401") (pin "2") (pintype "passive"))
      (node (ref "CW403") (pin "2") (pintype "passive"))
      (node (ref "CW405") (pin "3") (pintype "passive"))
    )
    (net (code "6") (name "/AI_CS324") (class "Default")
      (node (ref "C416") (pin "1") (pintype "passive"))
      (node (ref "IC403") (pin "6") (pinfunction "AIN2_6") (pintype "passive"))
      (node (ref "R444") (pin "2") (pintype "passive"))
      (node (ref "Tp417") (pin "1") (pinfunction "tp_1") (pintype "passive"))
    )
    (net (code "7") (name "/AI_FM315") (class "Default")
      (node (ref "C417") (pin "1") (pintype "passive"))
      (node (ref "IC402") (pin "6") (pinfunction "AIN2_6") (pintype "passive"))
      (node (ref "R452") (pin "2") (pintype "passive"))
      (node (ref "Tp419") (pin "1") (pinfunction "tp_1") (pintype "passive"))
    )
    (net (code "8") (name "/AI_MFC111") (class "Default")
      (node (ref "C407") (pin "1") (pintype "passive"))
      (node (ref "IC401") (pin "6") (pinfunction "AIN2_6") (pintype "passive"))
      (node (ref "R408") (pin "2") (pintype "passive"))
      (node (ref "Tp403") (pin "1") (pinfunction "tp_1") (pintype "passive"))
    )
    (net (code "9") (name "/AI_MFC121") (class "Default")
      (node (ref "C409") (pin "1") (pintype "passive"))
      (node (ref "IC401") (pin "7") (pinfunction "AIN3_7") (pintype "passive"))
      (node (ref "R417") (pin "2") (pintype "passive"))
      (node (ref "Tp406") (pin "1") (pinfunction "tp_1") (pintype "passive"))
    )
    (net (code "10") (name "/AI_MFM211") (class "Default")
      (node (ref "C411") (pin "1") (pintype "passive"))
      (node (ref "IC401") (pin "4") (pinfunction "AIN0_4") (pintype "passive"))
      (node (ref "R427") (pin "2") (pintype "passive"))
      (node (ref "Tp409") (pin "1") (pinfunction "tp_1") (pintype "passive"))
    )
    (net (code "11") (name "/AI_MFM222") (class "Default")
      (node (ref "C413") (pin "1") (pintype "passive"))
      (node (ref "IC401") (pin "5") (pinfunction "AIN1_5") (pintype "passive"))
      (node (ref "R435") (pin "2") (pintype "passive"))
      (node (ref "Tp412") (pin "1") (pinfunction "tp_1") (pintype "passive"))
    )
    (net (code "12") (name "/AI_MFM231") (class "Default")
      (node (ref "C415") (pin "1") (pintype "passive"))
      (node (ref "IC402") (pin "7") (pinfunction "AIN3_7") (pintype "passive"))
      (node (ref "R443") (pin "2") (pintype "passive"))
      (node (ref "Tp416") (pin "1") (pinfunction "tp_1") (pintype "passive"))
    )
    (net (code "13") (name "/AI_PT105") (class "Default")
      (node (ref "C402") (pin "1") (pintype "passive"))
      (node (ref "IC400") (pin "6") (pinfunction "AIN2_6") (pintype "passive"))
      (node (ref "R400") (pin "2") (pintype "passive"))
      (node (ref "Tp400") (pin "1") (pinfunction "tp_1") (pintype "passive"))
    )
    (net (code "14") (name "/AI_PT109") (class "Default")
      (node (ref "C410") (pin "1") (pintype "passive"))
      (node (ref "IC403") (pin "7") (pinfunction "AIN3_7") (pintype "passive"))
      (node (ref "R420") (pin "2") (pintype "passive"))
      (node (ref "Tp407") (pin "1") (pinfunction "tp_1") (pintype "passive"))
    )
    (net (code "15") (name "/AI_PT113") (class "Default")
      (node (ref "C412") (pin "1") (pintype "passive"))
      (node (ref "IC403") (pin "4") (pinfunction "AIN0_4") (pintype "passive"))
      (node (ref "R428") (pin "2") (pintype "passive"))
      (node (ref "Tp410") (pin "1") (pinfunction "tp_1") (pintype "passive"))
    )
    (net (code "16") (name "/AI_PT123") (class "Default")
      (node (ref "C414") (pin "1") (pintype "passive"))
      (node (ref "IC403") (pin "5") (pinfunction "AIN1_5") (pintype "passive"))
      (node (ref "R436") (pin "2") (pintype "passive"))
      (node (ref "Tp414") (pin "1") (pinfunction "tp_1") (pintype "passive"))
    )
    (net (code "17") (name "/AI_PT146") (class "Default")
      (node (ref "C405") (pin "1") (pintype "passive"))
      (node (ref "IC400") (pin "7") (pinfunction "AIN3_7") (pintype "passive"))
      (node (ref "R403") (pin "2") (pintype "passive"))
      (node (ref "Tp401") (pin "1") (pinfunction "tp_1") (pintype "passive"))
    )
    (net (code "18") (name "/AI_PT162") (class "Default")
      (node (ref "IC400") (pin "5") (pinfunction "AIN1_5") (pintype "passive"))
    )
    (net (code "19") (name "/AI_PT163") (class "Default")
      (node (ref "C406") (pin "1") (pintype "passive"))
      (node (ref "R406") (pin "2") (pintype "passive"))
      (node (ref "Tp402") (pin "1") (pinfunction "tp_1") (pintype "passive"))
    )
    (net (code "20") (name "/AI_PT383") (class "Default")
      (node (ref "C408") (pin "1") (pintype "passive"))
      (node (ref "IC400") (pin "4") (pinfunction "AIN0_4") (pintype "passive"))
      (node (ref "R414") (pin "2") (pintype "passive"))
      (node (ref "Tp404") (pin "1") (pinfunction "tp_1") (pintype "passive"))
    )
    (net (code "21") (name "/AI_spare1") (class "Default")
      (node (ref "C418") (pin "1") (pintype "passive"))
      (node (ref "IC402") (pin "5") (pinfunction "AIN1_5") (pintype "passive"))
      (node (ref "R453") (pin "2") (pintype "passive"))
      (node (ref "Tp420") (pin "1") (pinfunction "tp_1") (pintype "passive"))
    )
    (net (code "22") (name "/DI_FAN504") (class "Default")
      (node (ref "B400") (pin "4") (pinfunction "C_4") (pintype "passive"))
      (node (ref "R411") (pin "1") (pintype "passive"))
      (node (ref "Tp405") (pin "1") (pinfunction "tp_1") (pintype "passive"))
    )
    (net (code "23") (name "/DI_FD176") (class "Default")
      (node (ref "B405") (pin "4") (pinfunction "C_4") (pintype "passive"))
      (node (ref "R448") (pin "1") (pintype "passive"))
      (node (ref "Tp418") (pin "1") (pinfunction "tp_1") (pintype "passive"))
    )
    (net (code "24") (name "/DI_FIRE") (class "Default")
      (node (ref "R449") (pin "1") (pintype "passive"))
      (node (ref "R451") (pin "1") (pintype "passive"))
    )
    (net (code "25") (name "/DI_GD501") (class "Default")
      (node (ref "B401") (pin "4") (pinfunction "C_4") (pintype "passive"))
      (node (ref "R418") (pin "1") (pintype "passive"))
      (node (ref "Tp408") (pin "1") (pinfunction "tp_1") (pintype "passive"))
    )
    (net (code "26") (name "/DI_GD502") (class "Default")
      (node (ref "B402") (pin "4") (pinfunction "C_4") (pintype "passive"))
      (node (ref "R425") (pin "1") (pintype "passive"))
      (node (ref "Tp411") (pin "1") (pinfunction "tp_1") (pintype "passive"))
    )
    (net (code "27") (name "/DI_SPARE1") (class "Default")
      (node (ref "B404") (pin "4") (pinfunction "C_4") (pintype "passive"))
      (node (ref "R440") (pin "1") (pintype "passive"))
      (node (ref "Tp415") (pin "1") (pinfunction "tp_1") (pintype "passive"))
    )
    (net (code "28") (name "/DI_TJ_SIG") (class "Default")
      (node (ref "B403") (pin "4") (pinfunction "C_4") (pintype "passive"))
      (node (ref "R433") (pin "1") (pintype "passive"))
      (node (ref "Tp413") (pin "1") (pinfunction "tp_1") (pintype "passive"))
    )
    (net (code "29") (name "/FAN_ERR") (class "Default")
      (node (ref "B400") (pin "2") (pinfunction "K_2") (pintype "passive"))
    )
    (net (code "30") (name "/I2C_SCL") (class "Default")
      (node (ref "IC400") (pin "10") (pinfunction "SCL_10") (pintype "passive"))
      (node (ref "IC401") (pin "10") (pinfunction "SCL_10") (pintype "passive"))
      (node (ref "IC402") (pin "1") (pinfunction "ADDR_1") (pintype "passive"))
      (node (ref "IC402") (pin "10") (pinfunction "SCL_10") (pintype "passive"))
      (node (ref "IC403") (pin "10") (pinfunction "SCL_10") (pintype "passive"))
    )
    (net (code "31") (name "/I2C_SDA") (class "Default")
      (node (ref "IC400") (pin "9") (pinfunction "SDA_9") (pintype "passive"))
      (node (ref "IC401") (pin "1") (pinfunction "ADDR_1") (pintype "passive"))
      (node (ref "IC401") (pin "9") (pinfunction "SDA_9") (pintype "passive"))
      (node (ref "IC402") (pin "9") (pinfunction "SDA_9") (pintype "passive"))
      (node (ref "IC403") (pin "9") (pinfunction "SDA_9") (pintype "passive"))
    )
    (net (code "32") (name "/PAO_MFC111") (class "Default")
      (node (ref "CW406") (pin "2") (pintype "passive"))
    )
    (net (code "33") (name "/PAO_MFC121") (class "Default")
      (node (ref "CW408") (pin "2") (pintype "passive"))
    )
    (net (code "34") (name "/TC_AMB_1") (class "Default")
      (node (ref "IC402") (pin "4") (pinfunction "AIN0_4") (pintype "passive"))
    )
    (net (code "35") (name "AGND") (class "Default")
      (node (ref "C400") (pin "2") (pintype "passive"))
      (node (ref "C401") (pin "2") (pintype "passive"))
      (node (ref "C402") (pin "2") (pintype "passive"))
      (node (ref "C403") (pin "2") (pintype "passive"))
      (node (ref "C404") (pin "2") (pintype "passive"))
      (node (ref "C405") (pin "2") (pintype "passive"))
      (node (ref "C406") (pin "2") (pintype "passive"))
      (node (ref "C407") (pin "2") (pintype "passive"))
      (node (ref "C408") (pin "2") (pintype "passive"))
      (node (ref "C409") (pin "2") (pintype "passive"))
      (node (ref "C410") (pin "2") (pintype "passive"))
      (node (ref "C411") (pin "2") (pintype "passive"))
      (node (ref "C412") (pin "2") (pintype "passive"))
      (node (ref "C413") (pin "2") (pintype "passive"))
      (node (ref "C414") (pin "2") (pintype "passive"))
      (node (ref "C415") (pin "2") (pintype "passive"))
      (node (ref "C416") (pin "2") (pintype "passive"))
      (node (ref "C417") (pin "2") (pintype "passive"))
      (node (ref "C418") (pin "2") (pintype "passive"))
      (node (ref "CW419") (pin "3") (pintype "passive"))
      (node (ref "IC400") (pin "1") (pinfunction "ADDR_1") (pintype "passive"))
      (node (ref "IC400") (pin "3") (pinfunction "GND_3") (pintype "passive"))
      (node (ref "IC401") (pin "3") (pinfunction "GND_3") (pintype "passive"))
      (node (ref "IC402") (pin "3") (pinfunction "GND_3") (pintype "passive"))
      (node (ref "IC403") (pin "3") (pinfunction "GND_3") (pintype "passive"))
      (node (ref "R402") (pin "1") (pintype "passive"))
      (node (ref "R405") (pin "1") (pintype "passive"))
      (node (ref "R409") (pin "1") (pintype "passive"))
      (node (ref "R413") (pin "1") (pintype "passive"))
      (node (ref "R416") (pin "1") (pintype "passive"))
      (node (ref "R422") (pin "1") (pintype "passive"))
      (node (ref "R424") (pin "1") (pintype "passive"))
      (node (ref "R431") (pin "1") (pintype "passive"))
      (node (ref "R432") (pin "1") (pintype "passive"))
      (node (ref "R439") (pin "1") (pintype "passive"))
      (node (ref "R441") (pin "1") (pintype "passive"))
      (node (ref "R447") (pin "1") (pintype "passive"))
      (node (ref "R450") (pin "1") (pintype "passive"))
      (node (ref "R455") (pin "1") (pintype "passive"))
      (node (ref "R457") (pin "1") (pintype "passive"))
    )
    (net (code "36") (name "DGND") (class "Default")
      (node (ref "B400") (pin "3") (pinfunction "E_3") (pintype "passive"))
      (node (ref "B401") (pin "3") (pinfunction "E_3") (pintype "passive"))
      (node (ref "B402") (pin "3") (pinfunction "E_3") (pintype "passive"))
      (node (ref "B403") (pin "3") (pinfunction "E_3") (pintype "passive"))
      (node (ref "B404") (pin "3") (pinfunction "E_3") (pintype "passive"))
      (node (ref "B405") (pin "3") (pinfunction "E_3") (pintype "passive"))
      (node (ref "CW401") (pin "3") (pintype "passive"))
      (node (ref "CW403") (pin "3") (pintype "passive"))
    )
    (net (code "37") (name "Gnd_e") (class "Default")
      (node (ref "B401") (pin "2") (pinfunction "K_2") (pintype "passive"))
      (node (ref "B402") (pin "2") (pinfunction "K_2") (pintype "passive"))
      (node (ref "B403") (pin "2") (pinfunction "K_2") (pintype "passive"))
      (node (ref "B404") (pin "2") (pinfunction "K_2") (pintype "passive"))
      (node (ref "B405") (pin "2") (pinfunction "K_2") (pintype "passive"))
      (node (ref "CH400") (pin "1") (pintype "passive"))
      (node (ref "CH402") (pin "1") (pintype "passive"))
      (node (ref "CH404") (pin "1") (pintype "passive"))
      (node (ref "CH407") (pin "1") (pintype "passive"))
      (node (ref "CW400") (pin "3") (pintype "passive"))
      (node (ref "CW402") (pin "3") (pintype "passive"))
      (node (ref "CW404") (pin "3") (pintype "passive"))
      (node (ref "CW405") (pin "4") (pintype "passive"))
      (node (ref "CW406") (pin "4") (pintype "passive"))
      (node (ref "CW406") (pin "5") (pintype "passive"))
      (node (ref "CW407") (pin "3") (pintype "passive"))
      (node (ref "CW408") (pin "4") (pintype "passive"))
      (node (ref "CW408") (pin "5") (pintype "passive"))
      (node (ref "CW409") (pin "3") (pintype "passive"))
      (node (ref "CW410") (pin "3") (pintype "passive"))
      (node (ref "CW411") (pin "3") (pintype "passive"))
      (node (ref "CW412") (pin "3") (pintype "passive"))
      (node (ref "CW413") (pin "3") (pintype "passive"))
      (node (ref "CW414") (pin "3") (pintype "passive"))
      (node (ref "CW415") (pin "3") (pintype "passive"))
      (node (ref "CW416") (pin "3") (pintype "passive"))
      (node (ref "CW417") (pin "3") (pintype "passive"))
      (node (ref "CW418") (pin "3") (pintype "passive"))
      (node (ref "CW419") (pin "4") (pintype "passive"))
      (node (ref "CW420") (pin "3") (pintype "passive"))
      (node (ref "CW421") (pin "3") (pintype "passive"))
      (node (ref "D400") (pin "1") (pintype "passive"))
      (node (ref "D400") (pin "2") (pintype "passive"))
      (node (ref "D401") (pin "1") (pintype "passive"))
      (node (ref "D401") (pin "2") (pintype "passive"))
      (node (ref "D402") (pin "1") (pintype "passive"))
      (node (ref "D402") (pin "2") (pintype "passive"))
      (node (ref "D403") (pin "1") (pintype "passive"))
      (node (ref "D403") (pin "2") (pintype "passive"))
      (node (ref "D404") (pin "1") (pintype "passive"))
      (node (ref "D404") (pin "2") (pintype "passive"))
      (node (ref "D405") (pin "1") (pintype "passive"))
      (node (ref "D405") (pin "2") (pintype "passive"))
      (node (ref "D406") (pin "1") (pintype "passive"))
      (node (ref "D406") (pin "2") (pintype "passive"))
      (node (ref "D407") (pin "1") (pintype "passive"))
      (node (ref "D407") (pin "2") (pintype "passive"))
      (node (ref "D408") (pin "1") (pintype "passive"))
      (node (ref "D408") (pin "2") (pintype "passive"))
      (node (ref "D409") (pin "1") (pintype "passive"))
      (node (ref "D409") (pin "2") (pintype "passive"))
      (node (ref "D410") (pin "1") (pintype "passive"))
      (node (ref "D410") (pin "2") (pintype "passive"))
      (node (ref "D411") (pin "1") (pintype "passive"))
      (node (ref "D411") (pin "2") (pintype "passive"))
      (node (ref "D412") (pin "1") (pintype "passive"))
      (node (ref "D412") (pin "2") (pintype "passive"))
      (node (ref "D413") (pin "1") (pintype "passive"))
      (node (ref "D413") (pin "2") (pintype "passive"))
      (node (ref "D414") (pin "1") (pintype "passive"))
      (node (ref "D414") (pin "2") (pintype "passive"))
    )
    (net (code "38") (name "Net-(B400-A)") (class "Default")
      (node (ref "B400") (pin "1") (pinfunction "A_1") (pintype "passive"))
      (node (ref "R412") (pin "1") (pintype "passive"))
    )
    (net (code "39") (name "Net-(B401-A)") (class "Default")
      (node (ref "B401") (pin "1") (pinfunction "A_1") (pintype "passive"))
      (node (ref "R419") (pin "2") (pintype "passive"))
    )
    (net (code "40") (name "Net-(B402-A)") (class "Default")
      (node (ref "B402") (pin "1") (pinfunction "A_1") (pintype "passive"))
      (node (ref "R426") (pin "2") (pintype "passive"))
    )
    (net (code "41") (name "Net-(B403-A)") (class "Default")
      (node (ref "B403") (pin "1") (pinfunction "A_1") (pintype "passive"))
      (node (ref "R434") (pin "2") (pintype "passive"))
    )
    (net (code "42") (name "Net-(B404-A)") (class "Default")
      (node (ref "B404") (pin "1") (pinfunction "A_1") (pintype "passive"))
      (node (ref "R442") (pin "2") (pintype "passive"))
    )
    (net (code "43") (name "Net-(B405-A)") (class "Default")
      (node (ref "B405") (pin "1") (pinfunction "A_1") (pintype "passive"))
      (node (ref "R451") (pin "2") (pintype "passive"))
    )
    (net (code "44") (name "Net-(CW400-Pad2)") (class "Default")
      (node (ref "CW400") (pin "2") (pintype "passive"))
      (node (ref "D400") (pin "3") (pintype "passive"))
      (node (ref "R400") (pin "1") (pintype "passive"))
      (node (ref "R401") (pin "2") (pintype "passive"))
    )
    (net (code "45") (name "Net-(CW402-Pad2)") (class "Default")
      (node (ref "CW402") (pin "2") (pintype "passive"))
      (node (ref "D401") (pin "3") (pintype "passive"))
      (node (ref "R403") (pin "1") (pintype "passive"))
      (node (ref "R404") (pin "2") (pintype "passive"))
    )
    (net (code "46") (name "Net-(CW404-Pad2)") (class "Default")
      (node (ref "CW404") (pin "2") (pintype "passive"))
      (node (ref "D402") (pin "3") (pintype "passive"))
      (node (ref "R406") (pin "1") (pintype "passive"))
      (node (ref "R407") (pin "2") (pintype "passive"))
    )
    (net (code "47") (name "Net-(CW406-Pad3)") (class "Default")
      (node (ref "CW406") (pin "3") (pintype "passive"))
      (node (ref "D403") (pin "3") (pintype "passive"))
      (node (ref "R408") (pin "1") (pintype "passive"))
      (node (ref "R410") (pin "2") (pintype "passive"))
    )
    (net (code "48") (name "Net-(CW407-Pad2)") (class "Default")
      (node (ref "CW407") (pin "2") (pintype "passive"))
      (node (ref "D404") (pin "3") (pintype "passive"))
      (node (ref "R414") (pin "1") (pintype "passive"))
      (node (ref "R415") (pin "2") (pintype "passive"))
    )
    (net (code "49") (name "Net-(CW408-Pad3)") (class "Default")
      (node (ref "CW408") (pin "3") (pintype "passive"))
      (node (ref "D405") (pin "3") (pintype "passive"))
      (node (ref "R417") (pin "1") (pintype "passive"))
      (node (ref "R421") (pin "2") (pintype "passive"))
    )
    (net (code "50") (name "Net-(CW409-Pad2)") (class "Default")
      (node (ref "CW409") (pin "2") (pintype "passive"))
      (node (ref "R419") (pin "1") (pintype "passive"))
    )
    (net (code "51") (name "Net-(CW410-Pad2)") (class "Default")
      (node (ref "CW410") (pin "2") (pintype "passive"))
      (node (ref "D406") (pin "3") (pintype "passive"))
      (node (ref "R420") (pin "1") (pintype "passive"))
      (node (ref "R423") (pin "2") (pintype "passive"))
    )
    (net (code "52") (name "Net-(CW411-Pad2)") (class "Default")
      (node (ref "CW411") (pin "2") (pintype "passive"))
      (node (ref "R426") (pin "1") (pintype "passive"))
    )
    (net (code "53") (name "Net-(CW412-Pad2)") (class "Default")
      (node (ref "CW412") (pin "2") (pintype "passive"))
      (node (ref "D407") (pin "3") (pintype "passive"))
      (node (ref "R427") (pin "1") (pintype "passive"))
      (node (ref "R429") (pin "2") (pintype "passive"))
    )
    (net (code "54") (name "Net-(CW413-Pad2)") (class "Default")
      (node (ref "CW413") (pin "2") (pintype "passive"))
      (node (ref "D408") (pin "3") (pintype "passive"))
      (node (ref "R428") (pin "1") (pintype "passive"))
      (node (ref "R430") (pin "2") (pintype "passive"))
    )
    (net (code "55") (name "Net-(CW414-Pad2)") (class "Default")
      (node (ref "CW414") (pin "2") (pintype "passive"))
      (node (ref "R434") (pin "1") (pintype "passive"))
    )
    (net (code "56") (name "Net-(CW415-Pad2)") (class "Default")
      (node (ref "CW415") (pin "2") (pintype "passive"))
      (node (ref "D409") (pin "3") (pintype "passive"))
      (node (ref "R435") (pin "1") (pintype "passive"))
      (node (ref "R437") (pin "2") (pintype "passive"))
    )
    (net (code "57") (name "Net-(CW416-Pad2)") (class "Default")
      (node (ref "CW416") (pin "2") (pintype "passive"))
      (node (ref "D410") (pin "3") (pintype "passive"))
      (node (ref "R436") (pin "1") (pintype "passive"))
      (node (ref "R438") (pin "2") (pintype "passive"))
    )
    (net (code "58") (name "Net-(CW417-Pad2)") (class "Default")
      (node (ref "CW417") (pin "2") (pintype "passive"))
      (node (ref "R442") (pin "1") (pintype "passive"))
    )
    (net (code "59") (name "Net-(CW418-Pad2)") (class "Default")
      (node (ref "CW418") (pin "2") (pintype "passive"))
      (node (ref "D411") (pin "3") (pintype "passive"))
      (node (ref "R443") (pin "1") (pintype "passive"))
      (node (ref "R445") (pin "2") (pintype "passive"))
    )
    (net (code "60") (name "Net-(CW419-Pad2)") (class "Default")
      (node (ref "CW419") (pin "2") (pintype "passive"))
      (node (ref "D412") (pin "3") (pintype "passive"))
      (node (ref "R444") (pin "1") (pintype "passive"))
      (node (ref "R446") (pin "2") (pintype "passive"))
    )
    (net (code "61") (name "Net-(CW420-Pad2)") (class "Default")
      (node (ref "CW420") (pin "2") (pintype "passive"))
      (node (ref "D413") (pin "3") (pintype "passive"))
      (node (ref "R452") (pin "1") (pintype "passive"))
      (node (ref "R454") (pin "2") (pintype "passive"))
    )
    (net (code "62") (name "Net-(CW421-Pad2)") (class "Default")
      (node (ref "CW421") (pin "2") (pintype "passive"))
      (node (ref "D414") (pin "3") (pintype "passive"))
      (node (ref "R453") (pin "1") (pintype "passive"))
      (node (ref "R456") (pin "2") (pintype "passive"))
    )
    (net (code "63") (name "Net-(R401-Pad1)") (class "Default")
      (node (ref "R401") (pin "1") (pintype "passive"))
      (node (ref "R402") (pin "2") (pintype "passive"))
    )
    (net (code "64") (name "Net-(R404-Pad1)") (class "Default")
      (node (ref "R404") (pin "1") (pintype "passive"))
      (node (ref "R405") (pin "2") (pintype "passive"))
    )
    (net (code "65") (name "Net-(R407-Pad1)") (class "Default")
      (node (ref "R407") (pin "1") (pintype "passive"))
      (node (ref "R409") (pin "2") (pintype "passive"))
    )
    (net (code "66") (name "Net-(R410-Pad1)") (class "Default")
      (node (ref "R410") (pin "1") (pintype "passive"))
      (node (ref "R413") (pin "2") (pintype "passive"))
    )
    (net (code "67") (name "Net-(R415-Pad1)") (class "Default")
      (node (ref "R415") (pin "1") (pintype "passive"))
      (node (ref "R416") (pin "2") (pintype "passive"))
    )
    (net (code "68") (name "Net-(R421-Pad1)") (class "Default")
      (node (ref "R421") (pin "1") (pintype "passive"))
      (node (ref "R422") (pin "2") (pintype "passive"))
    )
    (net (code "69") (name "Net-(R423-Pad1)") (class "Default")
      (node (ref "R423") (pin "1") (pintype "passive"))
      (node (ref "R424") (pin "2") (pintype "passive"))
    )
    (net (code "70") (name "Net-(R429-Pad1)") (class "Default")
      (node (ref "R429") (pin "1") (pintype "passive"))
      (node (ref "R431") (pin "2") (pintype "passive"))
    )
    (net (code "71") (name "Net-(R430-Pad1)") (class "Default")
      (node (ref "R430") (pin "1") (pintype "passive"))
      (node (ref "R432") (pin "2") (pintype "passive"))
    )
    (net (code "72") (name "Net-(R437-Pad1)") (class "Default")
      (node (ref "R437") (pin "1") (pintype "passive"))
      (node (ref "R439") (pin "2") (pintype "passive"))
    )
    (net (code "73") (name "Net-(R438-Pad1)") (class "Default")
      (node (ref "R438") (pin "1") (pintype "passive"))
      (node (ref "R441") (pin "2") (pintype "passive"))
    )
    (net (code "74") (name "Net-(R445-Pad1)") (class "Default")
      (node (ref "R445") (pin "1") (pintype "passive"))
      (node (ref "R447") (pin "2") (pintype "passive"))
    )
    (net (code "75") (name "Net-(R446-Pad1)") (class "Default")
      (node (ref "R446") (pin "1") (pintype "passive"))
      (node (ref "R450") (pin "2") (pintype "passive"))
    )
    (net (code "76") (name "Net-(R454-Pad1)") (class "Default")
      (node (ref "R454") (pin "1") (pintype "passive"))
      (node (ref "R455") (pin "2") (pintype "passive"))
    )
    (net (code "77") (name "Net-(R456-Pad1)") (class "Default")
      (node (ref "R456") (pin "1") (pintype "passive"))
      (node (ref "R457") (pin "2") (pintype "passive"))
    )
    (net (code "78") (name "unconnected-(CH400-Pad2)") (class "Default")
      (node (ref "CH400") (pin "2") (pintype "passive"))
    )
    (net (code "79") (name "unconnected-(CH400-Pad3)") (class "Default")
      (node (ref "CH400") (pin "3") (pintype "passive"))
    )
    (net (code "80") (name "unconnected-(CH401-Pad1)") (class "Default")
      (node (ref "CH401") (pin "1") (pintype "passive"))
    )
    (net (code "81") (name "unconnected-(CH401-Pad2)") (class "Default")
      (node (ref "CH401") (pin "2") (pintype "passive"))
    )
    (net (code "82") (name "unconnected-(CH401-Pad3)") (class "Default")
      (node (ref "CH401") (pin "3") (pintype "passive"))
    )
    (net (code "83") (name "unconnected-(CH402-Pad2)") (class "Default")
      (node (ref "CH402") (pin "2") (pintype "passive"))
    )
    (net (code "84") (name "unconnected-(CH402-Pad3)") (class "Default")
      (node (ref "CH402") (pin "3") (pintype "passive"))
    )
    (net (code "85") (name "unconnected-(CH403-Pad1)") (class "Default")
      (node (ref "CH403") (pin "1") (pintype "passive"))
    )
    (net (code "86") (name "unconnected-(CH403-Pad2)") (class "Default")
      (node (ref "CH403") (pin "2") (pintype "passive"))
    )
    (net (code "87") (name "unconnected-(CH403-Pad3)") (class "Default")
      (node (ref "CH403") (pin "3") (pintype "passive"))
    )
    (net (code "88") (name "unconnected-(CH404-Pad2)") (class "Default")
      (node (ref "CH404") (pin "2") (pintype "passive"))
    )
    (net (code "89") (name "unconnected-(CH404-Pad3)") (class "Default")
      (node (ref "CH404") (pin "3") (pintype "passive"))
    )
    (net (code "90") (name "unconnected-(CH405-Pad1)") (class "Default")
      (node (ref "CH405") (pin "1") (pintype "passive"))
    )
    (net (code "91") (name "unconnected-(CH405-Pad2)") (class "Default")
      (node (ref "CH405") (pin "2") (pintype "passive"))
    )
    (net (code "92") (name "unconnected-(CH405-Pad3)") (class "Default")
      (node (ref "CH405") (pin "3") (pintype "passive"))
    )
    (net (code "93") (name "unconnected-(CH405-Pad4)") (class "Default")
      (node (ref "CH405") (pin "4") (pintype "passive"))
    )
    (net (code "94") (name "unconnected-(CH406-Pad1)") (class "Default")
      (node (ref "CH406") (pin "1") (pintype "passive"))
    )
    (net (code "95") (name "unconnected-(CH406-Pad2)") (class "Default")
      (node (ref "CH406") (pin "2") (pintype "passive"))
    )
    (net (code "96") (name "unconnected-(CH406-Pad3)") (class "Default")
      (node (ref "CH406") (pin "3") (pintype "passive"))
    )
    (net (code "97") (name "unconnected-(CH406-Pad4)") (class "Default")
      (node (ref "CH406") (pin "4") (pintype "passive"))
    )
    (net (code "98") (name "unconnected-(CH406-Pad5)") (class "Default")
      (node (ref "CH406") (pin "5") (pintype "passive"))
    )
    (net (code "99") (name "unconnected-(CH407-Pad2)") (class "Default")
      (node (ref "CH407") (pin "2") (pintype "passive"))
    )
    (net (code "100") (name "unconnected-(CH407-Pad3)") (class "Default")
      (node (ref "CH407") (pin "3") (pintype "passive"))
    )
    (net (code "101") (name "unconnected-(CH408-Pad1)") (class "Default")
      (node (ref "CH408") (pin "1") (pintype "passive"))
    )
    (net (code "102") (name "unconnected-(CH408-Pad2)") (class "Default")
      (node (ref "CH408") (pin "2") (pintype "passive"))
    )
    (net (code "103") (name "unconnected-(CH408-Pad3)") (class "Default")
      (node (ref "CH408") (pin "3") (pintype "passive"))
    )
    (net (code "104") (name "unconnected-(CH408-Pad4)") (class "Default")
      (node (ref "CH408") (pin "4") (pintype "passive"))
    )
    (net (code "105") (name "unconnected-(CH408-Pad5)") (class "Default")
      (node (ref "CH408") (pin "5") (pintype "passive"))
    )
    (net (code "106") (name "unconnected-(CH409-Pad1)") (class "Default")
      (node (ref "CH409") (pin "1") (pintype "passive"))
    )
    (net (code "107") (name "unconnected-(CH409-Pad2)") (class "Default")
      (node (ref "CH409") (pin "2") (pintype "passive"))
    )
    (net (code "108") (name "unconnected-(CH409-Pad3)") (class "Default")
      (node (ref "CH409") (pin "3") (pintype "passive"))
    )
    (net (code "109") (name "unconnected-(CH410-Pad1)") (class "Default")
      (node (ref "CH410") (pin "1") (pintype "passive"))
    )
    (net (code "110") (name "unconnected-(CH410-Pad2)") (class "Default")
      (node (ref "CH410") (pin "2") (pintype "passive"))
    )
    (net (code "111") (name "unconnected-(CH410-Pad3)") (class "Default")
      (node (ref "CH410") (pin "3") (pintype "passive"))
    )
    (net (code "112") (name "unconnected-(CH411-Pad1)") (class "Default")
      (node (ref "CH411") (pin "1") (pintype "passive"))
    )
    (net (code "113") (name "unconnected-(CH411-Pad2)") (class "Default")
      (node (ref "CH411") (pin "2") (pintype "passive"))
    )
    (net (code "114") (name "unconnected-(CH411-Pad3)") (class "Default")
      (node (ref "CH411") (pin "3") (pintype "passive"))
    )
    (net (code "115") (name "unconnected-(CH412-Pad1)") (class "Default")
      (node (ref "CH412") (pin "1") (pintype "passive"))
    )
    (net (code "116") (name "unconnected-(CH412-Pad2)") (class "Default")
      (node (ref "CH412") (pin "2") (pintype "passive"))
    )
    (net (code "117") (name "unconnected-(CH412-Pad3)") (class "Default")
      (node (ref "CH412") (pin "3") (pintype "passive"))
    )
    (net (code "118") (name "unconnected-(CH413-Pad1)") (class "Default")
      (node (ref "CH413") (pin "1") (pintype "passive"))
    )
    (net (code "119") (name "unconnected-(CH413-Pad2)") (class "Default")
      (node (ref "CH413") (pin "2") (pintype "passive"))
    )
    (net (code "120") (name "unconnected-(CH413-Pad3)") (class "Default")
      (node (ref "CH413") (pin "3") (pintype "passive"))
    )
    (net (code "121") (name "unconnected-(CH414-Pad1)") (class "Default")
      (node (ref "CH414") (pin "1") (pintype "passive"))
    )
    (net (code "122") (name "unconnected-(CH414-Pad2)") (class "Default")
      (node (ref "CH414") (pin "2") (pintype "passive"))
    )
    (net (code "123") (name "unconnected-(CH414-Pad3)") (class "Default")
      (node (ref "CH414") (pin "3") (pintype "passive"))
    )
    (net (code "124") (name "unconnected-(CH415-Pad1)") (class "Default")
      (node (ref "CH415") (pin "1") (pintype "passive"))
    )
    (net (code "125") (name "unconnected-(CH415-Pad2)") (class "Default")
      (node (ref "CH415") (pin "2") (pintype "passive"))
    )
    (net (code "126") (name "unconnected-(CH415-Pad3)") (class "Default")
      (node (ref "CH415") (pin "3") (pintype "passive"))
    )
    (net (code "127") (name "unconnected-(CH415-Pad4)") (class "Default")
      (node (ref "CH415") (pin "4") (pintype "passive"))
    )
    (net (code "128") (name "unconnected-(CH416-Pad1)") (class "Default")
      (node (ref "CH416") (pin "1") (pintype "passive"))
    )
    (net (code "129") (name "unconnected-(CH416-Pad2)") (class "Default")
      (node (ref "CH416") (pin "2") (pintype "passive"))
    )
    (net (code "130") (name "unconnected-(CH416-Pad3)") (class "Default")
      (node (ref "CH416") (pin "3") (pintype "passive"))
    )
    (net (code "131") (name "unconnected-(CH417-Pad1)") (class "Default")
      (node (ref "CH417") (pin "1") (pintype "passive"))
    )
    (net (code "132") (name "unconnected-(CH417-Pad2)") (class "Default")
      (node (ref "CH417") (pin "2") (pintype "passive"))
    )
    (net (code "133") (name "unconnected-(CH417-Pad3)") (class "Default")
      (node (ref "CH417") (pin "3") (pintype "passive"))
    )
    (net (code "134") (name "unconnected-(IC400-ALERT{slash}RDY-Pad2)") (class "Default")
      (node (ref "IC400") (pin "2") (pinfunction "ALERT/RDY_2") (pintype "passive"))
    )
    (net (code "135") (name "unconnected-(IC401-ALERT{slash}RDY-Pad2)") (class "Default")
      (node (ref "IC401") (pin "2") (pinfunction "ALERT/RDY_2") (pintype "passive"))
    )
    (net (code "136") (name "unconnected-(IC402-ALERT{slash}RDY-Pad2)") (class "Default")
      (node (ref "IC402") (pin "2") (pinfunction "ALERT/RDY_2") (pintype "passive"))
    )
    (net (code "137") (name "unconnected-(IC403-ALERT{slash}RDY-Pad2)") (class "Default")
      (node (ref "IC403") (pin "2") (pinfunction "ALERT/RDY_2") (pintype "passive"))
    )
  )
)
